# PL2303Module_Schematic.net
KiCad netlist of a schematic drawn in EAGLE
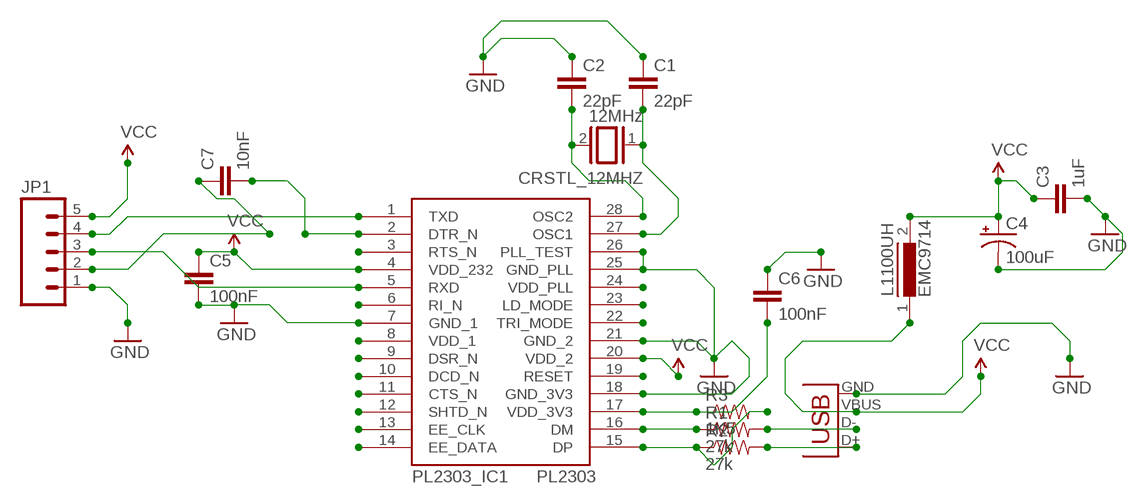
[diagram p0: schematic, sheet 1]

(export (version "E")
  (design (tool "Eeschema 10.0.6"))
  (components
    (comp (ref "C1")
      (value "22pF")
      (footprint "eagle-import:1206")
      (libsource (lib "eagle-import") (part "CAP1206"))
    )
    (comp (ref "C2")
      (value "22pF")
      (footprint "eagle-import:1206")
      (libsource (lib "eagle-import") (part "CAP1206"))
    )
    (comp (ref "C3")
      (value "1uF")
      (footprint "eagle-import:CAP-PTH-SMALL2")
      (libsource (lib "eagle-import") (part "SparkFun-Passives_CAPPTH2"))
    )
    (comp (ref "C4")
      (value "100uF")
      (footprint "eagle-import:CPOL-RADIAL-100UF-25V")
      (libsource (lib "eagle-import") (part "CAP_POLPTH1"))
    )
    (comp (ref "C5")
      (value "100nF")
      (footprint "eagle-import:CAP-PTH-SMALL2")
      (libsource (lib "eagle-import") (part "CAPPTH2"))
    )
    (comp (ref "C6")
      (value "100nF")
      (footprint "eagle-import:1206")
      (libsource (lib "eagle-import") (part "CAP1206"))
    )
    (comp (ref "C7")
      (value "10nF")
      (footprint "eagle-import:1206")
      (libsource (lib "eagle-import") (part "CAP1206"))
    )
    (comp (ref "CRSTL_12MHZ")
      (value "12MHz")
      (footprint "eagle-import:Q")
      (libsource (lib "eagle-import") (part "XTAL"))
    )
    (comp (ref "JP1")
      (value "M05PTH_LONGPADS")
      (footprint "eagle-import:1X05_LONGPADS")
      (libsource (lib "eagle-import") (part "M05PTH_LONGPADS"))
    )
    (comp (ref "L1100UH")
      (value "EMC9714")
      (footprint "eagle-import:EMC9714")
      (libsource (lib "eagle-import") (part "EMC9714"))
    )
    (comp (ref "PL2303_IC1")
      (value "PL2303-SSOP28")
      (footprint "eagle-import:PL2303-SSOP28")
      (libsource (lib "eagle-import") (part "PL2303-SSOP28"))
    )
    (comp (ref "R1")
      (value "27k")
      (footprint "eagle-import:0805")
      (libsource (lib "eagle-import") (part "RESISTOR0805-RES"))
    )
    (comp (ref "R2")
      (value "27k")
      (footprint "eagle-import:0805")
      (libsource (lib "eagle-import") (part "RESISTOR0805-RES"))
    )
    (comp (ref "R3")
      (value "1K5")
      (footprint "eagle-import:1206")
      (libsource (lib "eagle-import") (part "RESISTOR1206"))
    )
    (comp (ref "X1")
      (value "USBSMD")
      (footprint "eagle-import:USB-MINIB")
      (libsource (lib "eagle-import") (part "USBSMD"))
    )
  )
  (nets
    (net (code "1") (name "GND") (class "Default")
      (node (ref "C1") (pin "1") (pinfunction "1_1") (pintype "passive"))
      (node (ref "C2") (pin "1") (pinfunction "1_1") (pintype "passive"))
      (node (ref "C3") (pin "2") (pinfunction "2_2") (pintype "passive"))
      (node (ref "C4") (pin "2") (pinfunction "-_2") (pintype "passive"))
      (node (ref "C5") (pin "2") (pinfunction "2_2") (pintype "passive"))
      (node (ref "C6") (pin "1") (pinfunction "1_1") (pintype "passive"))
      (node (ref "JP1") (pin "1") (pinfunction "1_1") (pintype "passive"))
      (node (ref "PL2303_IC1") (pin "18") (pinfunction "GND_3V3_18") (pintype "bidirectional"))
      (node (ref "PL2303_IC1") (pin "21") (pinfunction "GND_2_21") (pintype "bidirectional"))
      (node (ref "PL2303_IC1") (pin "25") (pinfunction "GND_PLL_25") (pintype "bidirectional"))
      (node (ref "PL2303_IC1") (pin "26") (pinfunction "PLL_TEST_26") (pintype "bidirectional"))
      (node (ref "PL2303_IC1") (pin "7") (pinfunction "GND_1_7") (pintype "bidirectional"))
      (node (ref "X1") (pin "GND") (pinfunction "GND_GND") (pintype "bidirectional"))
    )
    (net (code "2") (name "Net-(C7-Pad1)") (class "Default")
      (node (ref "C7") (pin "1") (pinfunction "1_1") (pintype "passive"))
      (node (ref "JP1") (pin "2") (pinfunction "2_2") (pintype "passive"))
    )
    (net (code "3") (name "Net-(PL2303_IC1-DM)") (class "Default")
      (node (ref "PL2303_IC1") (pin "16") (pinfunction "DM_16") (pintype "bidirectional"))
      (node (ref "R1") (pin "1") (pinfunction "1_1") (pintype "passive"))
    )
    (net (code "4") (name "Net-(PL2303_IC1-DP)") (class "Default")
      (node (ref "PL2303_IC1") (pin "15") (pinfunction "DP_15") (pintype "bidirectional"))
      (node (ref "R2") (pin "1") (pinfunction "1_1") (pintype "passive"))
      (node (ref "R3") (pin "2") (pinfunction "2_2") (pintype "passive"))
    )
    (net (code "5") (name "Net-(PL2303_IC1-DTR_N)") (class "Default")
      (node (ref "C7") (pin "2") (pinfunction "2_2") (pintype "passive"))
      (node (ref "PL2303_IC1") (pin "2") (pinfunction "DTR_N_2") (pintype "bidirectional"))
    )
    (net (code "6") (name "Net-(PL2303_IC1-OSC1)") (class "Default")
      (node (ref "C1") (pin "2") (pinfunction "2_2") (pintype "passive"))
      (node (ref "CRSTL_12MHZ") (pin "1") (pinfunction "1_1") (pintype "passive"))
      (node (ref "PL2303_IC1") (pin "27") (pinfunction "OSC1_27") (pintype "bidirectional"))
    )
    (net (code "7") (name "Net-(PL2303_IC1-OSC2)") (class "Default")
      (node (ref "C2") (pin "2") (pinfunction "2_2") (pintype "passive"))
      (node (ref "CRSTL_12MHZ") (pin "2") (pinfunction "2_2") (pintype "passive"))
      (node (ref "PL2303_IC1") (pin "28") (pinfunction "OSC2_28") (pintype "bidirectional"))
    )
    (net (code "8") (name "Net-(PL2303_IC1-RXD)") (class "Default")
      (node (ref "JP1") (pin "3") (pinfunction "3_3") (pintype "passive"))
      (node (ref "PL2303_IC1") (pin "5") (pinfunction "RXD_5") (pintype "bidirectional"))
    )
    (net (code "9") (name "Net-(PL2303_IC1-TXD)") (class "Default")
      (node (ref "JP1") (pin "4") (pinfunction "4_4") (pintype "passive"))
      (node (ref "PL2303_IC1") (pin "1") (pinfunction "TXD_1") (pintype "bidirectional"))
    )
    (net (code "10") (name "Net-(PL2303_IC1-VDD_3V3)") (class "Default")
      (node (ref "C6") (pin "2") (pinfunction "2_2") (pintype "passive"))
      (node (ref "PL2303_IC1") (pin "17") (pinfunction "VDD_3V3_17") (pintype "bidirectional"))
      (node (ref "R3") (pin "1") (pinfunction "1_1") (pintype "passive"))
    )
    (net (code "11") (name "Net-(R1-Pad2)") (class "Default")
      (node (ref "R1") (pin "2") (pinfunction "2_2") (pintype "passive"))
      (node (ref "X1") (pin "D-") (pinfunction "D-_D-") (pintype "bidirectional"))
    )
    (net (code "12") (name "Net-(R2-Pad2)") (class "Default")
      (node (ref "R2") (pin "2") (pinfunction "2_2") (pintype "passive"))
      (node (ref "X1") (pin "D+") (pinfunction "D+_D+") (pintype "bidirectional"))
    )
    (net (code "13") (name "VCC") (class "Default")
      (node (ref "C3") (pin "1") (pinfunction "1_1") (pintype "passive"))
      (node (ref "C4") (pin "1") (pinfunction "+_1") (pintype "passive"))
      (node (ref "C5") (pin "1") (pinfunction "1_1") (pintype "passive"))
      (node (ref "JP1") (pin "5") (pinfunction "5_5") (pintype "passive"))
      (node (ref "L1100UH") (pin "1") (pinfunction "1_1") (pintype "passive"))
      (node (ref "L1100UH") (pin "2") (pinfunction "2_2") (pintype "passive"))
      (node (ref "PL2303_IC1") (pin "20") (pinfunction "VDD_2_20") (pintype "bidirectional"))
      (node (ref "PL2303_IC1") (pin "4") (pinfunction "VDD_232_4") (pintype "bidirectional"))
      (node (ref "X1") (pin "VBUS") (pinfunction "VBUS_VBUS") (pintype "bidirectional"))
    )
    (net (code "14") (name "unconnected-(PL2303_IC1-CTS_N-Pad11)") (class "Default")
      (node (ref "PL2303_IC1") (pin "11") (pinfunction "CTS_N_11") (pintype "bidirectional"))
    )
    (net (code "15") (name "unconnected-(PL2303_IC1-DCD_N-Pad10)") (class "Default")
      (node (ref "PL2303_IC1") (pin "10") (pinfunction "DCD_N_10") (pintype "bidirectional"))
    )
    (net (code "16") (name "unconnected-(PL2303_IC1-DSR_N-Pad9)") (class "Default")
      (node (ref "PL2303_IC1") (pin "9") (pinfunction "DSR_N_9") (pintype "bidirectional"))
    )
    (net (code "17") (name "unconnected-(PL2303_IC1-EE_CLK-Pad13)") (class "Default")
      (node (ref "PL2303_IC1") (pin "13") (pinfunction "EE_CLK_13") (pintype "bidirectional"))
    )
    (net (code "18") (name "unconnected-(PL2303_IC1-EE_DATA-Pad14)") (class "Default")
      (node (ref "PL2303_IC1") (pin "14") (pinfunction "EE_DATA_14") (pintype "bidirectional"))
    )
    (net (code "19") (name "unconnected-(PL2303_IC1-LD_MODE-Pad23)") (class "Default")
      (node (ref "PL2303_IC1") (pin "23") (pinfunction "LD_MODE_23") (pintype "bidirectional"))
    )
    (net (code "20") (name "unconnected-(PL2303_IC1-RESET-Pad19)") (class "Default")
      (node (ref "PL2303_IC1") (pin "19") (pinfunction "RESET_19") (pintype "bidirectional"))
    )
    (net (code "21") (name "unconnected-(PL2303_IC1-RI_N-Pad6)") (class "Default")
      (node (ref "PL2303_IC1") (pin "6") (pinfunction "RI_N_6") (pintype "bidirectional"))
    )
    (net (code "22") (name "unconnected-(PL2303_IC1-RTS_N-Pad3)") (class "Default")
      (node (ref "PL2303_IC1") (pin "3") (pinfunction "RTS_N_3") (pintype "bidirectional"))
    )
    (net (code "23") (name "unconnected-(PL2303_IC1-SHTD_N-Pad12)") (class "Default")
      (node (ref "PL2303_IC1") (pin "12") (pinfunction "SHTD_N_12") (pintype "bidirectional"))
    )
    (net (code "24") (name "unconnected-(PL2303_IC1-TRI_MODE-Pad22)") (class "Default")
      (node (ref "PL2303_IC1") (pin "22") (pinfunction "TRI_MODE_22") (pintype "bidirectional"))
    )
    (net (code "25") (name "unconnected-(PL2303_IC1-VDD_1-Pad8)") (class "Default")
      (node (ref "PL2303_IC1") (pin "8") (pinfunction "VDD_1_8") (pintype "bidirectional"))
    )
    (net (code "26") (name "unconnected-(PL2303_IC1-VDD_PLL-Pad24)") (class "Default")
      (node (ref "PL2303_IC1") (pin "24") (pinfunction "VDD_PLL_24") (pintype "bidirectional"))
    )
  )
)
